# lightSensor_ALS-PT19-315C_Breakout.net
KiCad netlist of a schematic drawn in EAGLE
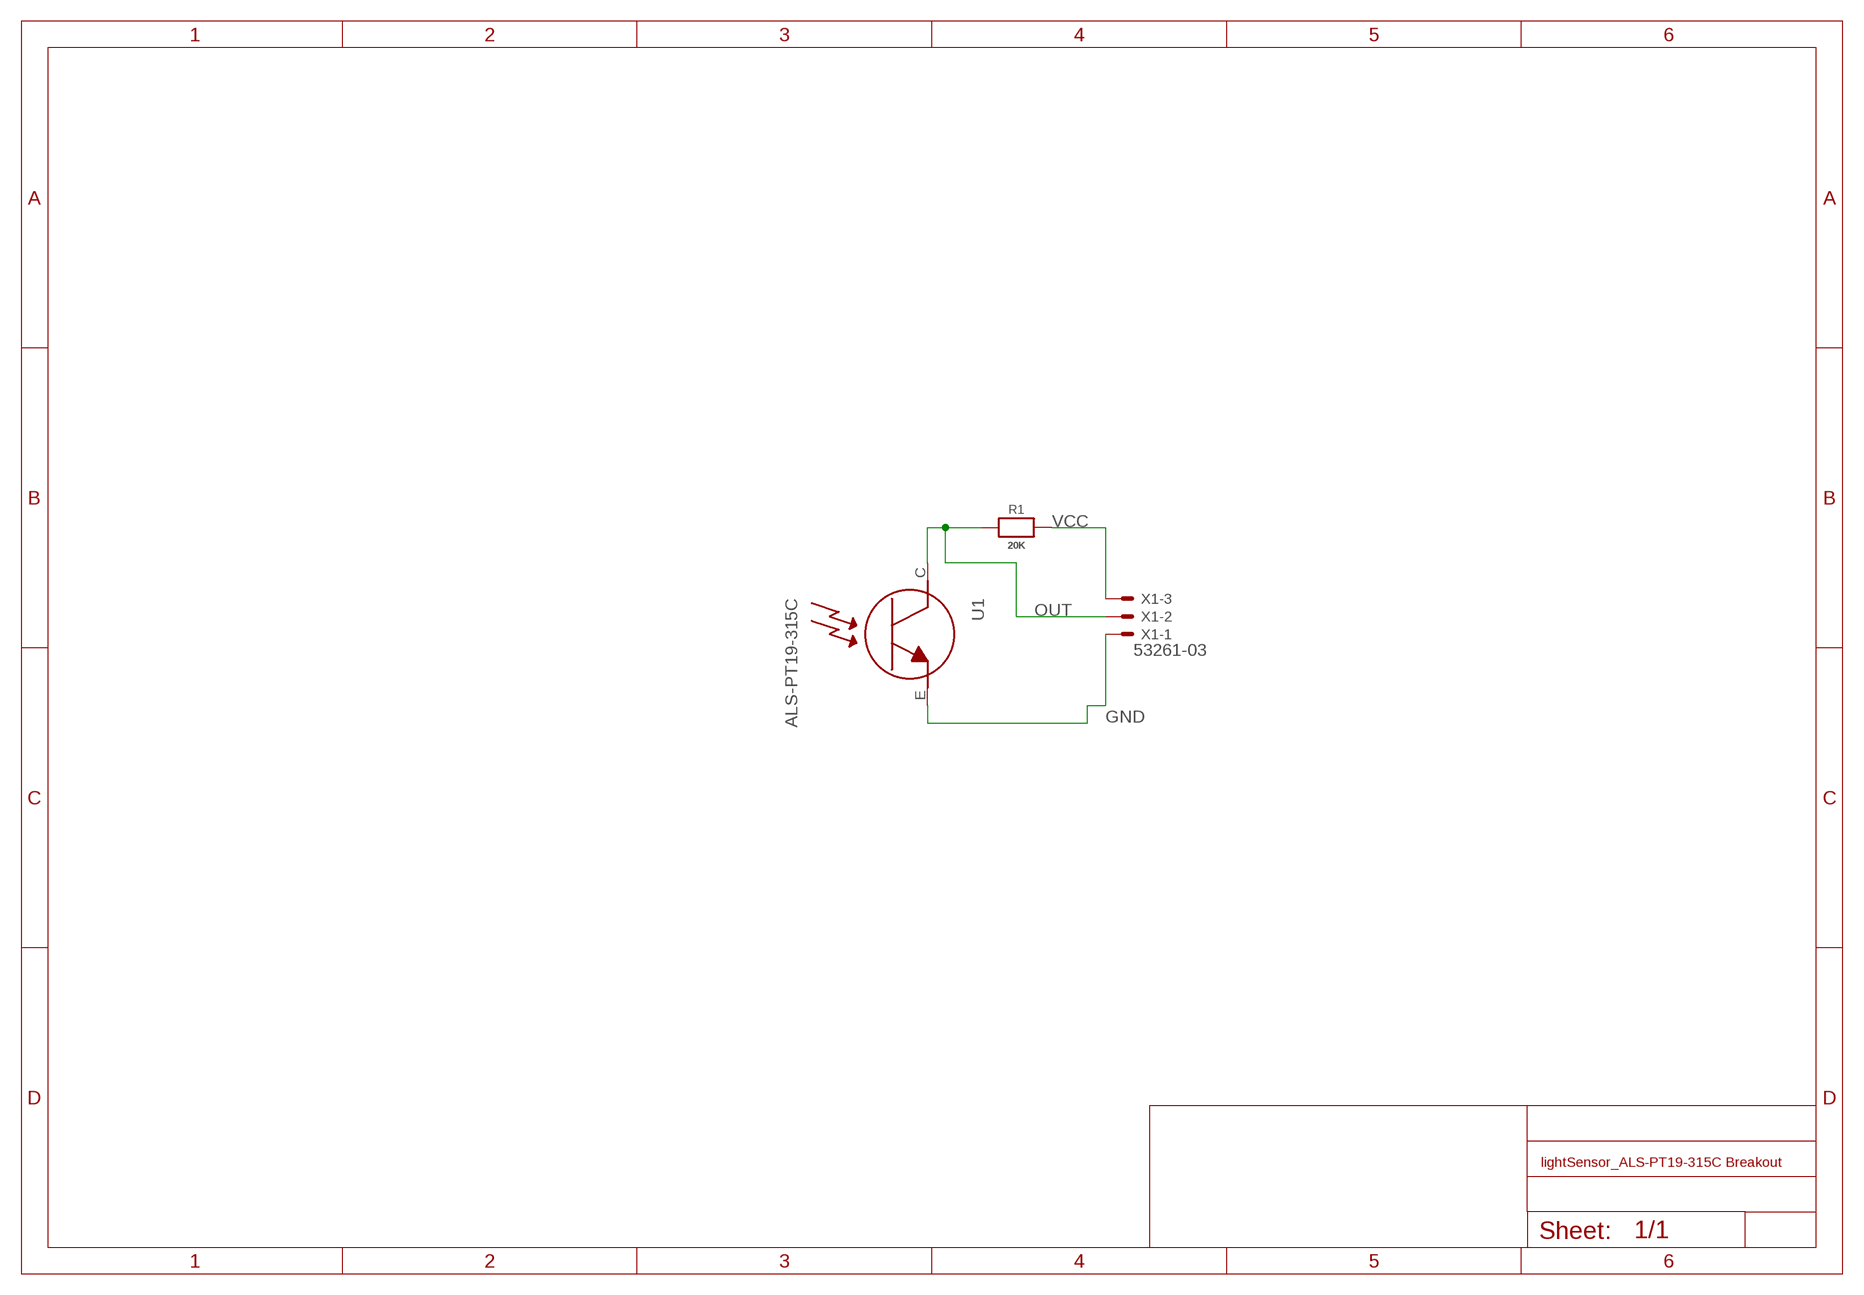
[diagram p0: schematic, sheet 1]

(export (version "E")
  (design (tool "Eeschema 10.0.6"))
  (components
    (comp (ref "R1")
      (value "20K")
      (footprint "eagle-import:0603-NO")
      (libsource (lib "eagle-import") (part "RESISTOR_0603_NOOUT"))
    )
    (comp (ref "U1")
      (value "ALS-PT19-315C")
      (footprint "eagle-import:ALS-PT19-315C")
      (libsource (lib "eagle-import") (part "LIGHT_ALS-PT19-315C"))
    )
    (comp (ref "X1")
      (value "53261-03")
      (footprint "eagle-import:53261-03")
      (fields (field (name "MF") "MOLEX") (field (name "MPN") "53261-0390"))
      (libsource (lib "eagle-import") (part "53?-03261"))
    )
  )
  (nets
    (net (code "1") (name "/GND") (class "Default")
      (node (ref "U1") (pin "E") (pinfunction "E_E") (pintype "bidirectional"))
      (node (ref "X1") (pin "1") (pinfunction "S_1") (pintype "passive"))
    )
    (net (code "2") (name "/OUT") (class "Default")
      (node (ref "R1") (pin "2") (pinfunction "2_2") (pintype "passive"))
      (node (ref "U1") (pin "C") (pinfunction "C_C") (pintype "bidirectional"))
      (node (ref "X1") (pin "2") (pinfunction "S_2") (pintype "passive"))
    )
    (net (code "3") (name "/VCC") (class "Default")
      (node (ref "R1") (pin "1") (pinfunction "1_1") (pintype "passive"))
      (node (ref "X1") (pin "3") (pinfunction "S_3") (pintype "passive"))
    )
  )
)
